# zero_board.net
KiCad netlist of a schematic drawn in EAGLE
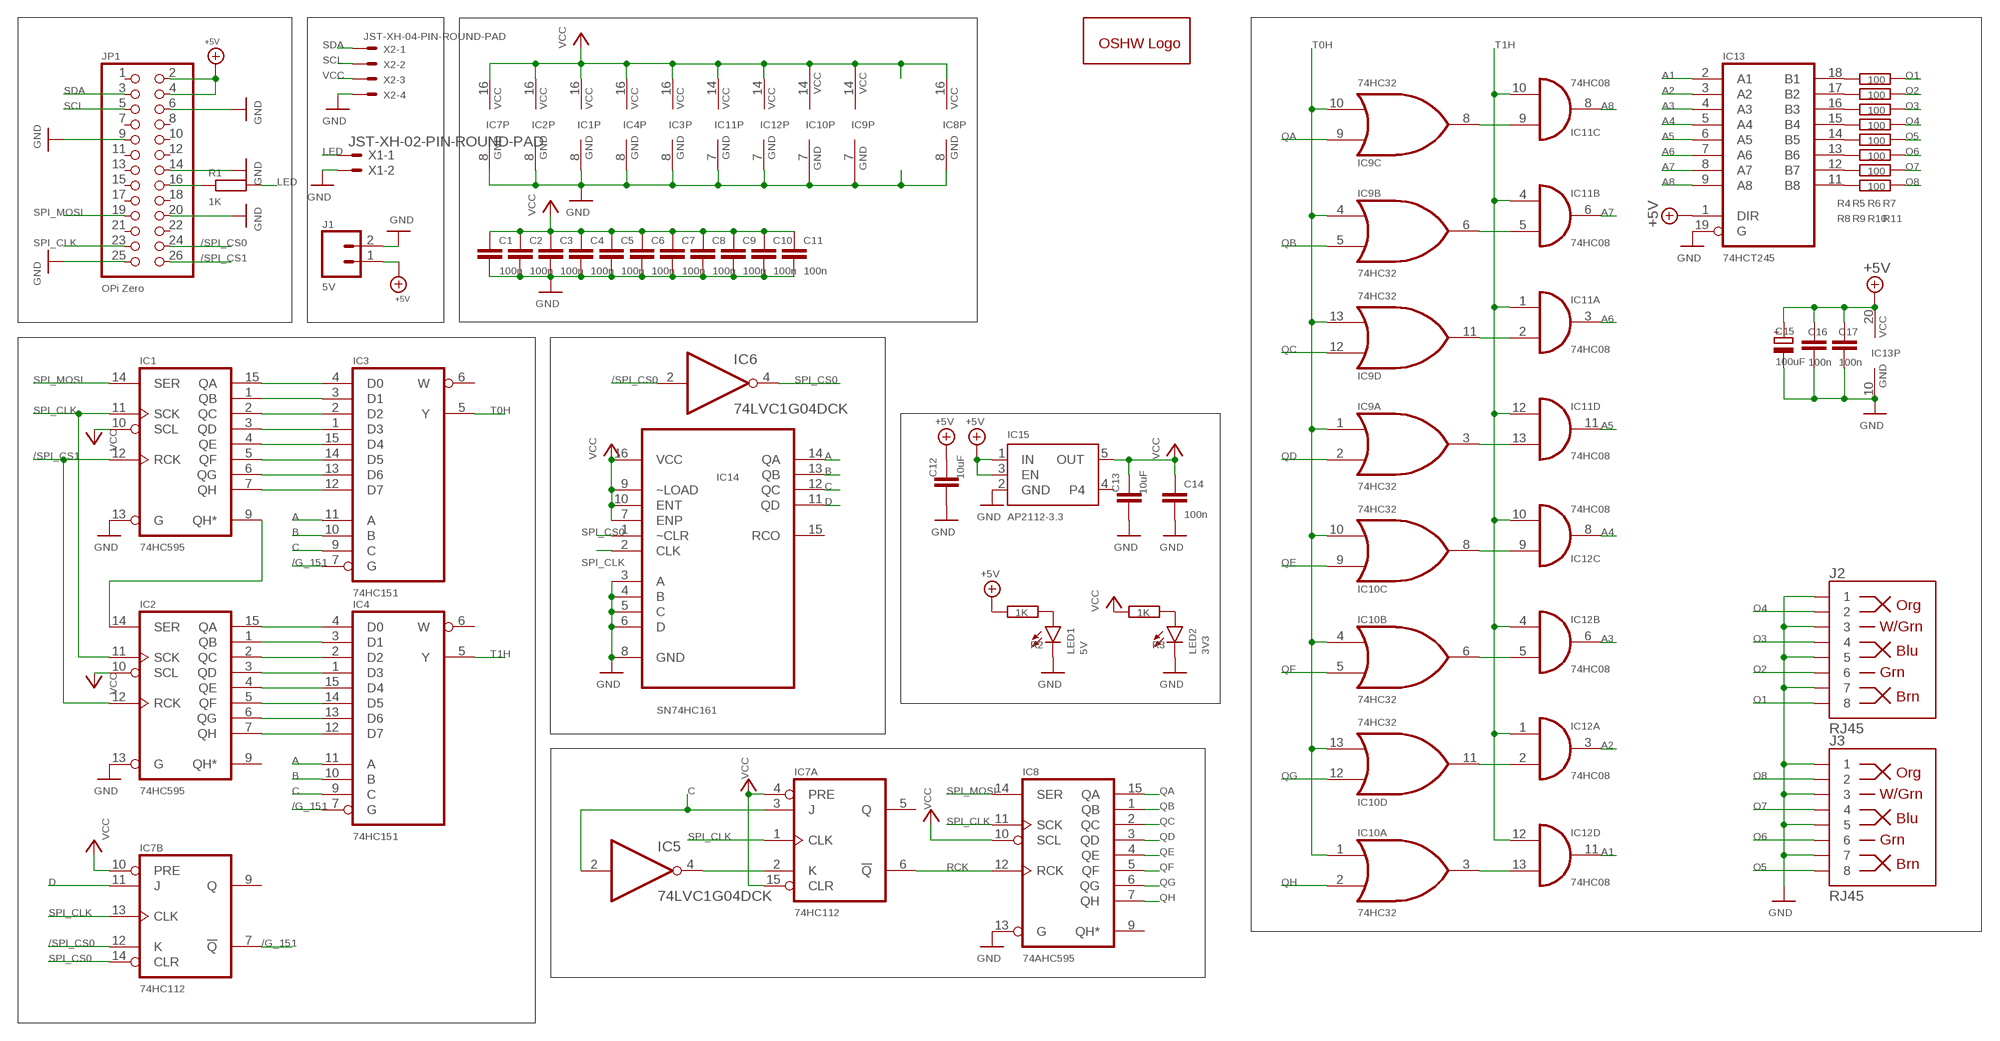
[diagram p0: schematic, sheet 1]

(export (version "E")
  (design (tool "Eeschema 10.0.6"))
  (components
    (comp (ref "C1")
      (value "100n")
      (footprint "eagle-import:C0603")
      (libsource (lib "eagle-import") (part "C-EUC0603"))
    )
    (comp (ref "C2")
      (value "100n")
      (footprint "eagle-import:C0603")
      (libsource (lib "eagle-import") (part "C-EUC0603"))
    )
    (comp (ref "C3")
      (value "100n")
      (footprint "eagle-import:C0603")
      (libsource (lib "eagle-import") (part "C-EUC0603"))
    )
    (comp (ref "C4")
      (value "100n")
      (footprint "eagle-import:C0603")
      (libsource (lib "eagle-import") (part "C-EUC0603"))
    )
    (comp (ref "C5")
      (value "100n")
      (footprint "eagle-import:C0603")
      (libsource (lib "eagle-import") (part "C-EUC0603"))
    )
    (comp (ref "C6")
      (value "100n")
      (footprint "eagle-import:C0603")
      (libsource (lib "eagle-import") (part "C-EUC0603"))
    )
    (comp (ref "C7")
      (value "100n")
      (footprint "eagle-import:C0603")
      (libsource (lib "eagle-import") (part "C-EUC0603"))
    )
    (comp (ref "C8")
      (value "100n")
      (footprint "eagle-import:C0603")
      (libsource (lib "eagle-import") (part "C-EUC0603"))
    )
    (comp (ref "C9")
      (value "100n")
      (footprint "eagle-import:C0603")
      (libsource (lib "eagle-import") (part "C-EUC0603"))
    )
    (comp (ref "C10")
      (value "100n")
      (footprint "eagle-import:C0603")
      (libsource (lib "eagle-import") (part "C-EUC0603"))
    )
    (comp (ref "C11")
      (value "100n")
      (footprint "eagle-import:C0603")
      (libsource (lib "eagle-import") (part "C-EUC0603"))
    )
    (comp (ref "C12")
      (value "10uF")
      (footprint "eagle-import:C0805")
      (libsource (lib "eagle-import") (part "C-EUC0805"))
    )
    (comp (ref "C13")
      (value "10uF")
      (footprint "eagle-import:C0805")
      (libsource (lib "eagle-import") (part "C-EUC0805"))
    )
    (comp (ref "C14")
      (value "100n")
      (footprint "eagle-import:C0603")
      (libsource (lib "eagle-import") (part "C-EUC0603"))
    )
    (comp (ref "C15")
      (value "100uF")
      (footprint "eagle-import:E2,5-5")
      (libsource (lib "eagle-import") (part "CPOL-EUE2.5-5"))
    )
    (comp (ref "C16")
      (value "100n")
      (footprint "eagle-import:C0603")
      (libsource (lib "eagle-import") (part "C-EUC0603"))
    )
    (comp (ref "C17")
      (value "100n")
      (footprint "eagle-import:C0603")
      (libsource (lib "eagle-import") (part "C-EUC0603"))
    )
    (comp (ref "GOLD_ORB_SM1")
      (value "OSHWLOGOLOGO5MM")
      (footprint "eagle-import:OSHW_5MM")
      (libsource (lib "eagle-import") (part "OSHWLOGOLOGO5MM"))
    )
    (comp (ref "IC1")
      (value "74HC595")
      (footprint "eagle-import:SO16")
      (libsource (lib "eagle-import") (part "74595DHC"))
    )
    (comp (ref "IC2")
      (value "74HC595")
      (footprint "eagle-import:SO16")
      (libsource (lib "eagle-import") (part "74595DHC"))
    )
    (comp (ref "IC3")
      (value "74HC151")
      (footprint "eagle-import:SO16")
      (libsource (lib "eagle-import") (part "74151DHC"))
    )
    (comp (ref "IC4")
      (value "74HC151")
      (footprint "eagle-import:SO16")
      (libsource (lib "eagle-import") (part "74151DHC"))
    )
    (comp (ref "IC5")
      (value "74LVC1G04DCK")
      (footprint "eagle-import:SC70-5")
      (libsource (lib "eagle-import") (part "741G04DCKLVC"))
    )
    (comp (ref "IC6")
      (value "74LVC1G04DCK")
      (footprint "eagle-import:SC70-5")
      (libsource (lib "eagle-import") (part "741G04DCKLVC"))
    )
    (comp (ref "IC7")
      (value "74HC112")
      (footprint "eagle-import:SO16")
      (libsource (lib "eagle-import") (part "74112DHC"))
    )
    (comp (ref "IC8")
      (value "74AHC595")
      (footprint "eagle-import:SO16")
      (libsource (lib "eagle-import") (part "74595DHC"))
    )
    (comp (ref "IC9")
      (value "74HC32")
      (footprint "eagle-import:SO14")
      (libsource (lib "eagle-import") (part "7432DLS"))
    )
    (comp (ref "IC10")
      (value "74HC32")
      (footprint "eagle-import:SO14")
      (libsource (lib "eagle-import") (part "7432DLS"))
    )
    (comp (ref "IC11")
      (value "74HC08")
      (footprint "eagle-import:SO14")
      (libsource (lib "eagle-import") (part "7408DHC"))
    )
    (comp (ref "IC12")
      (value "74HC08")
      (footprint "eagle-import:SO14")
      (libsource (lib "eagle-import") (part "7408DHC"))
    )
    (comp (ref "IC13")
      (value "74HCT245")
      (footprint "eagle-import:SO20W")
      (libsource (lib "eagle-import") (part "74245DWACT"))
    )
    (comp (ref "IC14")
      (value "SN74HC161")
      (footprint "eagle-import:SOIC127P600X175-16N")
      (fields (field (name "MF") "Texas Instruments") (field (name "MP") "SN74HC161DR"))
      (libsource (lib "eagle-import") (part "SN74HC161DR"))
    )
    (comp (ref "IC15")
      (value "AP2112-3.3")
      (footprint "eagle-import:SOT23-5")
      (libsource (lib "eagle-import") (part "VREG_SOT23-5"))
    )
    (comp (ref "J1")
      (value "5V")
      (footprint "eagle-import:SCREWTERMINAL-3.5MM-2")
      (libsource (lib "eagle-import") (part "CONN_023.5MM"))
    )
    (comp (ref "J2")
      (value "RJ45")
      (footprint "eagle-import:RJ45-8")
      (libsource (lib "eagle-import") (part "RJ45-8"))
    )
    (comp (ref "J3")
      (value "RJ45")
      (footprint "eagle-import:RJ45-8")
      (libsource (lib "eagle-import") (part "RJ45-8"))
    )
    (comp (ref "JP1")
      (value "OPi Zero")
      (footprint "eagle-import:2X13")
      (libsource (lib "eagle-import") (part "PINHD-2X13"))
    )
    (comp (ref "LED1")
      (value "5V")
      (footprint "eagle-import:CHIP-LED0603")
      (libsource (lib "eagle-import") (part "LEDCHIP-LED0603"))
    )
    (comp (ref "LED2")
      (value "3V3")
      (footprint "eagle-import:CHIP-LED0603")
      (libsource (lib "eagle-import") (part "LEDCHIP-LED0603"))
    )
    (comp (ref "R1")
      (value "1K")
      (footprint "eagle-import:R0603")
      (libsource (lib "eagle-import") (part "R-EU_R0603"))
    )
    (comp (ref "R2")
      (value "1K")
      (footprint "eagle-import:R0603")
      (libsource (lib "eagle-import") (part "R-EU_R0603"))
    )
    (comp (ref "R3")
      (value "1K")
      (footprint "eagle-import:R0603")
      (libsource (lib "eagle-import") (part "R-EU_R0603"))
    )
    (comp (ref "R4")
      (value "100")
      (footprint "eagle-import:R0603")
      (libsource (lib "eagle-import") (part "R-EU_R0603"))
    )
    (comp (ref "R5")
      (value "100")
      (footprint "eagle-import:R0603")
      (libsource (lib "eagle-import") (part "R-EU_R0603"))
    )
    (comp (ref "R6")
      (value "100")
      (footprint "eagle-import:R0603")
      (libsource (lib "eagle-import") (part "R-EU_R0603"))
    )
    (comp (ref "R7")
      (value "100")
      (footprint "eagle-import:R0603")
      (libsource (lib "eagle-import") (part "R-EU_R0603"))
    )
    (comp (ref "R8")
      (value "100")
      (footprint "eagle-import:R0603")
      (libsource (lib "eagle-import") (part "R-EU_R0603"))
    )
    (comp (ref "R9")
      (value "100")
      (footprint "eagle-import:R0603")
      (libsource (lib "eagle-import") (part "R-EU_R0603"))
    )
    (comp (ref "R10")
      (value "100")
      (footprint "eagle-import:R0603")
      (libsource (lib "eagle-import") (part "R-EU_R0603"))
    )
    (comp (ref "R11")
      (value "100")
      (footprint "eagle-import:R0603")
      (libsource (lib "eagle-import") (part "R-EU_R0603"))
    )
    (comp (ref "X1")
      (value "JST-XH-02-PIN-ROUND-PAD")
      (footprint "eagle-import:JST-XH-02-PACKAGE-ROUND-PAD")
      (libsource (lib "eagle-import") (part "JST-XH-02-PIN-ROUND-PAD"))
    )
    (comp (ref "X2")
      (value "JST-XH-04-PIN-ROUND-PAD")
      (footprint "eagle-import:JST-XH-04-PACKAGE-ROUND-PAD")
      (libsource (lib "eagle-import") (part "JST-XH-04-PIN-ROUND-PAD"))
    )
  )
  (nets
    (net (code "1") (name "+5V") (class "Default")
      (node (ref "C12") (pin "1") (pinfunction "1_1") (pintype "passive"))
      (node (ref "C15") (pin "+") (pinfunction "+_+") (pintype "passive"))
      (node (ref "C16") (pin "1") (pinfunction "1_1") (pintype "passive"))
      (node (ref "C17") (pin "1") (pinfunction "1_1") (pintype "passive"))
      (node (ref "IC13") (pin "1") (pinfunction "DIR_1") (pintype "input"))
      (node (ref "IC13") (pin "20") (pinfunction "VCC_20") (pintype "power_in"))
      (node (ref "IC15") (pin "1") (pinfunction "IN_1") (pintype "power_in"))
      (node (ref "IC15") (pin "3") (pinfunction "EN_3") (pintype "input"))
      (node (ref "J1") (pin "1") (pinfunction "1_1") (pintype "passive"))
      (node (ref "JP1") (pin "2") (pinfunction "2_2") (pintype "passive"))
      (node (ref "JP1") (pin "4") (pinfunction "4_4") (pintype "passive"))
      (node (ref "R2") (pin "1") (pinfunction "1_1") (pintype "passive"))
    )
    (net (code "2") (name "/A") (class "Default")
      (node (ref "IC14") (pin "14") (pinfunction "QA_14") (pintype "output"))
      (node (ref "IC3") (pin "11") (pinfunction "A_11") (pintype "input"))
      (node (ref "IC4") (pin "11") (pinfunction "A_11") (pintype "input"))
    )
    (net (code "3") (name "/A1") (class "Default")
      (node (ref "IC12") (pin "11") (pinfunction "O_11") (pintype "output"))
      (node (ref "IC13") (pin "2") (pinfunction "A1_2") (pintype "bidirectional"))
    )
    (net (code "4") (name "/A2") (class "Default")
      (node (ref "IC12") (pin "3") (pinfunction "O_3") (pintype "output"))
      (node (ref "IC13") (pin "3") (pinfunction "A2_3") (pintype "bidirectional"))
    )
    (net (code "5") (name "/A3") (class "Default")
      (node (ref "IC12") (pin "6") (pinfunction "O_6") (pintype "output"))
      (node (ref "IC13") (pin "4") (pinfunction "A3_4") (pintype "bidirectional"))
    )
    (net (code "6") (name "/A4") (class "Default")
      (node (ref "IC12") (pin "8") (pinfunction "O_8") (pintype "output"))
      (node (ref "IC13") (pin "5") (pinfunction "A4_5") (pintype "bidirectional"))
    )
    (net (code "7") (name "/A5") (class "Default")
      (node (ref "IC11") (pin "11") (pinfunction "O_11") (pintype "output"))
      (node (ref "IC13") (pin "6") (pinfunction "A5_6") (pintype "bidirectional"))
    )
    (net (code "8") (name "/A6") (class "Default")
      (node (ref "IC11") (pin "3") (pinfunction "O_3") (pintype "output"))
      (node (ref "IC13") (pin "7") (pinfunction "A6_7") (pintype "bidirectional"))
    )
    (net (code "9") (name "/A7") (class "Default")
      (node (ref "IC11") (pin "6") (pinfunction "O_6") (pintype "output"))
      (node (ref "IC13") (pin "8") (pinfunction "A7_8") (pintype "bidirectional"))
    )
    (net (code "10") (name "/A8") (class "Default")
      (node (ref "IC11") (pin "8") (pinfunction "O_8") (pintype "output"))
      (node (ref "IC13") (pin "9") (pinfunction "A8_9") (pintype "bidirectional"))
    )
    (net (code "11") (name "/B") (class "Default")
      (node (ref "IC14") (pin "13") (pinfunction "QB_13") (pintype "output"))
      (node (ref "IC3") (pin "10") (pinfunction "B_10") (pintype "input"))
      (node (ref "IC4") (pin "10") (pinfunction "B_10") (pintype "input"))
    )
    (net (code "12") (name "/C") (class "Default")
      (node (ref "IC14") (pin "12") (pinfunction "QC_12") (pintype "output"))
      (node (ref "IC3") (pin "9") (pinfunction "C_9") (pintype "input"))
      (node (ref "IC4") (pin "9") (pinfunction "C_9") (pintype "input"))
      (node (ref "IC5") (pin "2") (pinfunction "I_2") (pintype "input"))
      (node (ref "IC7") (pin "3") (pinfunction "J_3") (pintype "input"))
    )
    (net (code "13") (name "/D") (class "Default")
      (node (ref "IC14") (pin "11") (pinfunction "QD_11") (pintype "output"))
      (node (ref "IC7") (pin "11") (pinfunction "J_11") (pintype "input"))
    )
    (net (code "14") (name "/LED") (class "Default")
      (node (ref "R1") (pin "2") (pinfunction "2_2") (pintype "passive"))
      (node (ref "X1") (pin "1") (pinfunction "S_1") (pintype "passive"))
    )
    (net (code "15") (name "/O1") (class "Default")
      (node (ref "J2") (pin "8") (pinfunction "8_8") (pintype "bidirectional"))
      (node (ref "R4") (pin "2") (pinfunction "2_2") (pintype "passive"))
    )
    (net (code "16") (name "/O2") (class "Default")
      (node (ref "J2") (pin "6") (pinfunction "6_6") (pintype "bidirectional"))
      (node (ref "R5") (pin "2") (pinfunction "2_2") (pintype "passive"))
    )
    (net (code "17") (name "/O3") (class "Default")
      (node (ref "J2") (pin "4") (pinfunction "4_4") (pintype "bidirectional"))
      (node (ref "R6") (pin "2") (pinfunction "2_2") (pintype "passive"))
    )
    (net (code "18") (name "/O4") (class "Default")
      (node (ref "J2") (pin "2") (pinfunction "2_2") (pintype "bidirectional"))
      (node (ref "R7") (pin "2") (pinfunction "2_2") (pintype "passive"))
    )
    (net (code "19") (name "/O5") (class "Default")
      (node (ref "J3") (pin "8") (pinfunction "8_8") (pintype "bidirectional"))
      (node (ref "R8") (pin "2") (pinfunction "2_2") (pintype "passive"))
    )
    (net (code "20") (name "/O6") (class "Default")
      (node (ref "J3") (pin "6") (pinfunction "6_6") (pintype "bidirectional"))
      (node (ref "R9") (pin "2") (pinfunction "2_2") (pintype "passive"))
    )
    (net (code "21") (name "/O7") (class "Default")
      (node (ref "J3") (pin "4") (pinfunction "4_4") (pintype "bidirectional"))
      (node (ref "R10") (pin "2") (pinfunction "2_2") (pintype "passive"))
    )
    (net (code "22") (name "/O8") (class "Default")
      (node (ref "J3") (pin "2") (pinfunction "2_2") (pintype "bidirectional"))
      (node (ref "R11") (pin "2") (pinfunction "2_2") (pintype "passive"))
    )
    (net (code "23") (name "/QA") (class "Default")
      (node (ref "IC8") (pin "15") (pinfunction "QA_15") (pintype "tri_state"))
      (node (ref "IC9") (pin "9") (pinfunction "I0_9") (pintype "input"))
    )
    (net (code "24") (name "/QB") (class "Default")
      (node (ref "IC8") (pin "1") (pinfunction "QB_1") (pintype "tri_state"))
      (node (ref "IC9") (pin "5") (pinfunction "I1_5") (pintype "input"))
    )
    (net (code "25") (name "/QC") (class "Default")
      (node (ref "IC8") (pin "2") (pinfunction "QC_2") (pintype "tri_state"))
      (node (ref "IC9") (pin "12") (pinfunction "I0_12") (pintype "input"))
    )
    (net (code "26") (name "/QD") (class "Default")
      (node (ref "IC8") (pin "3") (pinfunction "QD_3") (pintype "tri_state"))
      (node (ref "IC9") (pin "2") (pinfunction "I1_2") (pintype "input"))
    )
    (net (code "27") (name "/QE") (class "Default")
      (node (ref "IC10") (pin "9") (pinfunction "I0_9") (pintype "input"))
      (node (ref "IC8") (pin "4") (pinfunction "QE_4") (pintype "tri_state"))
    )
    (net (code "28") (name "/QF") (class "Default")
      (node (ref "IC10") (pin "5") (pinfunction "I1_5") (pintype "input"))
      (node (ref "IC8") (pin "5") (pinfunction "QF_5") (pintype "tri_state"))
    )
    (net (code "29") (name "/QG") (class "Default")
      (node (ref "IC10") (pin "12") (pinfunction "I0_12") (pintype "input"))
      (node (ref "IC8") (pin "6") (pinfunction "QG_6") (pintype "tri_state"))
    )
    (net (code "30") (name "/QH") (class "Default")
      (node (ref "IC10") (pin "2") (pinfunction "I1_2") (pintype "input"))
      (node (ref "IC8") (pin "7") (pinfunction "QH_7") (pintype "tri_state"))
    )
    (net (code "31") (name "/RCK") (class "Default")
      (node (ref "IC7") (pin "6") (pinfunction "~{Q}_6") (pintype "output"))
      (node (ref "IC8") (pin "12") (pinfunction "RCK_12") (pintype "input"))
    )
    (net (code "32") (name "/SCL") (class "Default")
      (node (ref "JP1") (pin "5") (pinfunction "5_5") (pintype "passive"))
      (node (ref "X2") (pin "2") (pinfunction "S_2") (pintype "passive"))
    )
    (net (code "33") (name "/SDA") (class "Default")
      (node (ref "JP1") (pin "3") (pinfunction "3_3") (pintype "passive"))
      (node (ref "X2") (pin "1") (pinfunction "S_1") (pintype "passive"))
    )
    (net (code "34") (name "/SPI_CLK") (class "Default")
      (node (ref "IC1") (pin "11") (pinfunction "SCK_11") (pintype "input"))
      (node (ref "IC14") (pin "2") (pinfunction "CLK_2") (pintype "input"))
      (node (ref "IC2") (pin "11") (pinfunction "SCK_11") (pintype "input"))
      (node (ref "IC7") (pin "1") (pinfunction "CLK_1") (pintype "input"))
      (node (ref "IC7") (pin "13") (pinfunction "CLK_13") (pintype "input"))
      (node (ref "IC8") (pin "11") (pinfunction "SCK_11") (pintype "input"))
      (node (ref "JP1") (pin "23") (pinfunction "23_23") (pintype "passive"))
    )
    (net (code "35") (name "/SPI_CS0") (class "Default")
      (node (ref "IC14") (pin "1") (pinfunction "~{CLR}_1") (pintype "input"))
      (node (ref "IC6") (pin "4") (pinfunction "O_4") (pintype "output"))
      (node (ref "IC7") (pin "14") (pinfunction "CLR_14") (pintype "input"))
    )
    (net (code "36") (name "/SPI_MOSI") (class "Default")
      (node (ref "IC1") (pin "14") (pinfunction "SER_14") (pintype "input"))
      (node (ref "IC8") (pin "14") (pinfunction "SER_14") (pintype "input"))
      (node (ref "JP1") (pin "19") (pinfunction "19_19") (pintype "passive"))
    )
    (net (code "37") (name "/T0H") (class "Default")
      (node (ref "IC10") (pin "1") (pinfunction "I0_1") (pintype "input"))
      (node (ref "IC10") (pin "10") (pinfunction "I1_10") (pintype "input"))
      (node (ref "IC10") (pin "13") (pinfunction "I1_13") (pintype "input"))
      (node (ref "IC10") (pin "4") (pinfunction "I0_4") (pintype "input"))
      (node (ref "IC3") (pin "5") (pinfunction "Y_5") (pintype "output"))
      (node (ref "IC9") (pin "1") (pinfunction "I0_1") (pintype "input"))
      (node (ref "IC9") (pin "10") (pinfunction "I1_10") (pintype "input"))
      (node (ref "IC9") (pin "13") (pinfunction "I1_13") (pintype "input"))
      (node (ref "IC9") (pin "4") (pinfunction "I0_4") (pintype "input"))
    )
    (net (code "38") (name "/T1H") (class "Default")
      (node (ref "IC11") (pin "1") (pinfunction "I0_1") (pintype "input"))
      (node (ref "IC11") (pin "10") (pinfunction "I1_10") (pintype "input"))
      (node (ref "IC11") (pin "12") (pinfunction "I0_12") (pintype "input"))
      (node (ref "IC11") (pin "4") (pinfunction "I0_4") (pintype "input"))
      (node (ref "IC12") (pin "1") (pinfunction "I0_1") (pintype "input"))
      (node (ref "IC12") (pin "10") (pinfunction "I1_10") (pintype "input"))
      (node (ref "IC12") (pin "12") (pinfunction "I0_12") (pintype "input"))
      (node (ref "IC12") (pin "4") (pinfunction "I0_4") (pintype "input"))
      (node (ref "IC4") (pin "5") (pinfunction "Y_5") (pintype "output"))
    )
    (net (code "39") (name "/{slash}G_151") (class "Default")
      (node (ref "IC3") (pin "7") (pinfunction "G_7") (pintype "input"))
      (node (ref "IC4") (pin "7") (pinfunction "G_7") (pintype "input"))
      (node (ref "IC7") (pin "7") (pinfunction "~{Q}_7") (pintype "output"))
    )
    (net (code "40") (name "/{slash}SPI_CS0") (class "Default")
      (node (ref "IC6") (pin "2") (pinfunction "I_2") (pintype "input"))
      (node (ref "IC7") (pin "12") (pinfunction "K_12") (pintype "input"))
      (node (ref "JP1") (pin "24") (pinfunction "24_24") (pintype "passive"))
    )
    (net (code "41") (name "/{slash}SPI_CS1") (class "Default")
      (node (ref "IC1") (pin "12") (pinfunction "RCK_12") (pintype "input"))
      (node (ref "IC2") (pin "12") (pinfunction "RCK_12") (pintype "input"))
      (node (ref "JP1") (pin "26") (pinfunction "26_26") (pintype "passive"))
    )
    (net (code "42") (name "GND") (class "Default")
      (node (ref "C1") (pin "2") (pinfunction "2_2") (pintype "passive"))
      (node (ref "C10") (pin "2") (pinfunction "2_2") (pintype "passive"))
      (node (ref "C11") (pin "2") (pinfunction "2_2") (pintype "passive"))
      (node (ref "C12") (pin "2") (pinfunction "2_2") (pintype "passive"))
      (node (ref "C13") (pin "2") (pinfunction "2_2") (pintype "passive"))
      (node (ref "C14") (pin "2") (pinfunction "2_2") (pintype "passive"))
      (node (ref "C15") (pin "-") (pinfunction "-_-") (pintype "passive"))
      (node (ref "C16") (pin "2") (pinfunction "2_2") (pintype "passive"))
      (node (ref "C17") (pin "2") (pinfunction "2_2") (pintype "passive"))
      (node (ref "C2") (pin "2") (pinfunction "2_2") (pintype "passive"))
      (node (ref "C3") (pin "2") (pinfunction "2_2") (pintype "passive"))
      (node (ref "C4") (pin "2") (pinfunction "2_2") (pintype "passive"))
      (node (ref "C5") (pin "2") (pinfunction "2_2") (pintype "passive"))
      (node (ref "C6") (pin "2") (pinfunction "2_2") (pintype "passive"))
      (node (ref "C7") (pin "2") (pinfunction "2_2") (pintype "passive"))
      (node (ref "C8") (pin "2") (pinfunction "2_2") (pintype "passive"))
      (node (ref "C9") (pin "2") (pinfunction "2_2") (pintype "passive"))
      (node (ref "IC1") (pin "13") (pinfunction "G_13") (pintype "input"))
      (node (ref "IC1") (pin "8") (pinfunction "GND_8") (pintype "power_in"))
      (node (ref "IC10") (pin "7") (pinfunction "GND_7") (pintype "power_in"))
      (node (ref "IC11") (pin "7") (pinfunction "GND_7") (pintype "power_in"))
      (node (ref "IC12") (pin "7") (pinfunction "GND_7") (pintype "power_in"))
      (node (ref "IC13") (pin "10") (pinfunction "GND_10") (pintype "power_in"))
      (node (ref "IC13") (pin "19") (pinfunction "G_19") (pintype "input"))
      (node (ref "IC14") (pin "3") (pinfunction "A_3") (pintype "input"))
      (node (ref "IC14") (pin "4") (pinfunction "B_4") (pintype "input"))
      (node (ref "IC14") (pin "5") (pinfunction "C_5") (pintype "input"))
      (node (ref "IC14") (pin "6") (pinfunction "D_6") (pintype "input"))
      (node (ref "IC14") (pin "8") (pinfunction "GND_8") (pintype "passive"))
      (node (ref "IC15") (pin "2") (pinfunction "GND_2") (pintype "power_in"))
      (node (ref "IC2") (pin "13") (pinfunction "G_13") (pintype "input"))
      (node (ref "IC2") (pin "8") (pinfunction "GND_8") (pintype "power_in"))
      (node (ref "IC3") (pin "8") (pinfunction "GND_8") (pintype "power_in"))
      (node (ref "IC4") (pin "8") (pinfunction "GND_8") (pintype "power_in"))
      (node (ref "IC7") (pin "8") (pinfunction "GND_8") (pintype "power_in"))
      (node (ref "IC8") (pin "13") (pinfunction "G_13") (pintype "input"))
      (node (ref "IC8") (pin "8") (pinfunction "GND_8") (pintype "power_in"))
      (node (ref "IC9") (pin "7") (pinfunction "GND_7") (pintype "power_in"))
      (node (ref "J1") (pin "2") (pinfunction "2_2") (pintype "passive"))
      (node (ref "J2") (pin "1") (pinfunction "1_1") (pintype "bidirectional"))
      (node (ref "J2") (pin "3") (pinfunction "3_3") (pintype "bidirectional"))
      (node (ref "J2") (pin "5") (pinfunction "5_5") (pintype "bidirectional"))
      (node (ref "J2") (pin "7") (pinfunction "7_7") (pintype "bidirectional"))
      (node (ref "J3") (pin "1") (pinfunction "1_1") (pintype "bidirectional"))
      (node (ref "J3") (pin "3") (pinfunction "3_3") (pintype "bidirectional"))
      (node (ref "J3") (pin "5") (pinfunction "5_5") (pintype "bidirectional"))
      (node (ref "J3") (pin "7") (pinfunction "7_7") (pintype "bidirectional"))
      (node (ref "JP1") (pin "14") (pinfunction "14_14") (pintype "passive"))
      (node (ref "JP1") (pin "20") (pinfunction "20_20") (pintype "passive"))
      (node (ref "JP1") (pin "25") (pinfunction "25_25") (pintype "passive"))
      (node (ref "JP1") (pin "6") (pinfunction "6_6") (pintype "passive"))
      (node (ref "JP1") (pin "9") (pinfunction "9_9") (pintype "passive"))
      (node (ref "LED1") (pin "C") (pinfunction "C_C") (pintype "passive"))
      (node (ref "LED2") (pin "C") (pinfunction "C_C") (pintype "passive"))
      (node (ref "X1") (pin "2") (pinfunction "S_2") (pintype "passive"))
      (node (ref "X2") (pin "4") (pinfunction "S_4") (pintype "passive"))
    )
    (net (code "43") (name "Net-(IC1A-QA)") (class "Default")
      (node (ref "IC1") (pin "15") (pinfunction "QA_15") (pintype "tri_state"))
      (node (ref "IC3") (pin "4") (pinfunction "D0_4") (pintype "input"))
    )
    (net (code "44") (name "Net-(IC1A-QB)") (class "Default")
      (node (ref "IC1") (pin "1") (pinfunction "QB_1") (pintype "tri_state"))
      (node (ref "IC3") (pin "3") (pinfunction "D1_3") (pintype "input"))
    )
    (net (code "45") (name "Net-(IC1A-QC)") (class "Default")
      (node (ref "IC1") (pin "2") (pinfunction "QC_2") (pintype "tri_state"))
      (node (ref "IC3") (pin "2") (pinfunction "D2_2") (pintype "input"))
    )
    (net (code "46") (name "Net-(IC1A-QD)") (class "Default")
      (node (ref "IC1") (pin "3") (pinfunction "QD_3") (pintype "tri_state"))
      (node (ref "IC3") (pin "1") (pinfunction "D3_1") (pintype "input"))
    )
    (net (code "47") (name "Net-(IC1A-QE)") (class "Default")
      (node (ref "IC1") (pin "4") (pinfunction "QE_4") (pintype "tri_state"))
      (node (ref "IC3") (pin "15") (pinfunction "D4_15") (pintype "input"))
    )
    (net (code "48") (name "Net-(IC1A-QF)") (class "Default")
      (node (ref "IC1") (pin "5") (pinfunction "QF_5") (pintype "tri_state"))
      (node (ref "IC3") (pin "14") (pinfunction "D5_14") (pintype "input"))
    )
    (net (code "49") (name "Net-(IC1A-QG)") (class "Default")
      (node (ref "IC1") (pin "6") (pinfunction "QG_6") (pintype "tri_state"))
      (node (ref "IC3") (pin "13") (pinfunction "D6_13") (pintype "input"))
    )
    (net (code "50") (name "Net-(IC1A-QH)") (class "Default")
      (node (ref "IC1") (pin "7") (pinfunction "QH_7") (pintype "tri_state"))
      (node (ref "IC3") (pin "12") (pinfunction "D7_12") (pintype "input"))
    )
    (net (code "51") (name "Net-(IC1A-QH*)") (class "Default")
      (node (ref "IC1") (pin "9") (pinfunction "QH*_9") (pintype "tri_state"))
      (node (ref "IC2") (pin "14") (pinfunction "SER_14") (pintype "input"))
    )
    (net (code "52") (name "Net-(IC2A-QA)") (class "Default")
      (node (ref "IC2") (pin "15") (pinfunction "QA_15") (pintype "tri_state"))
      (node (ref "IC4") (pin "4") (pinfunction "D0_4") (pintype "input"))
    )
    (net (code "53") (name "Net-(IC2A-QB)") (class "Default")
      (node (ref "IC2") (pin "1") (pinfunction "QB_1") (pintype "tri_state"))
      (node (ref "IC4") (pin "3") (pinfunction "D1_3") (pintype "input"))
    )
    (net (code "54") (name "Net-(IC2A-QC)") (class "Default")
      (node (ref "IC2") (pin "2") (pinfunction "QC_2") (pintype "tri_state"))
      (node (ref "IC4") (pin "2") (pinfunction "D2_2") (pintype "input"))
    )
    (net (code "55") (name "Net-(IC2A-QD)") (class "Default")
      (node (ref "IC2") (pin "3") (pinfunction "QD_3") (pintype "tri_state"))
      (node (ref "IC4") (pin "1") (pinfunction "D3_1") (pintype "input"))
    )
    (net (code "56") (name "Net-(IC2A-QE)") (class "Default")
      (node (ref "IC2") (pin "4") (pinfunction "QE_4") (pintype "tri_state"))
      (node (ref "IC4") (pin "15") (pinfunction "D4_15") (pintype "input"))
    )
    (net (code "57") (name "Net-(IC2A-QF)") (class "Default")
      (node (ref "IC2") (pin "5") (pinfunction "QF_5") (pintype "tri_state"))
      (node (ref "IC4") (pin "14") (pinfunction "D5_14") (pintype "input"))
    )
    (net (code "58") (name "Net-(IC2A-QG)") (class "Default")
      (node (ref "IC2") (pin "6") (pinfunction "QG_6") (pintype "tri_state"))
      (node (ref "IC4") (pin "13") (pinfunction "D6_13") (pintype "input"))
    )
    (net (code "59") (name "Net-(IC2A-QH)") (class "Default")
      (node (ref "IC2") (pin "7") (pinfunction "QH_7") (pintype "tri_state"))
      (node (ref "IC4") (pin "12") (pinfunction "D7_12") (pintype "input"))
    )
    (net (code "60") (name "Net-(IC5A-O)") (class "Default")
      (node (ref "IC5") (pin "4") (pinfunction "O_4") (pintype "output"))
      (node (ref "IC7") (pin "2") (pinfunction "K_2") (pintype "input"))
    )
    (net (code "61") (name "Net-(IC10A-O)") (class "Default")
      (node (ref "IC10") (pin "3") (pinfunction "O_3") (pintype "output"))
      (node (ref "IC12") (pin "13") (pinfunction "I1_13") (pintype "input"))
    )
    (net (code "62") (name "Net-(IC10B-O)") (class "Default")
      (node (ref "IC10") (pin "6") (pinfunction "O_6") (pintype "output"))
      (node (ref "IC12") (pin "5") (pinfunction "I1_5") (pintype "input"))
    )
    (net (code "63") (name "Net-(IC10C-O)") (class "Default")
      (node (ref "IC10") (pin "8") (pinfunction "O_8") (pintype "output"))
      (node (ref "IC12") (pin "9") (pinfunction "I0_9") (pintype "input"))
    )
    (net (code "64") (name "Net-(IC10D-O)") (class "Default")
      (node (ref "IC10") (pin "11") (pinfunction "O_11") (pintype "output"))
      (node (ref "IC12") (pin "2") (pinfunction "I1_2") (pintype "input"))
    )
    (net (code "65") (name "Net-(IC11A-I1)") (class "Default")
      (node (ref "IC11") (pin "2") (pinfunction "I1_2") (pintype "input"))
      (node (ref "IC9") (pin "11") (pinfunction "O_11") (pintype "output"))
    )
    (net (code "66") (name "Net-(IC11B-I1)") (class "Default")
      (node (ref "IC11") (pin "5") (pinfunction "I1_5") (pintype "input"))
      (node (ref "IC9") (pin "6") (pinfunction "O_6") (pintype "output"))
    )
    (net (code "67") (name "Net-(IC11C-I0)") (class "Default")
      (node (ref "IC11") (pin "9") (pinfunction "I0_9") (pintype "input"))
      (node (ref "IC9") (pin "8") (pinfunction "O_8") (pintype "output"))
    )
    (net (code "68") (name "Net-(IC11D-I1)") (class "Default")
      (node (ref "IC11") (pin "13") (pinfunction "I1_13") (pintype "input"))
      (node (ref "IC9") (pin "3") (pinfunction "O_3") (pintype "output"))
    )
    (net (code "69") (name "Net-(IC13A-B1)") (class "Default")
      (node (ref "IC13") (pin "18") (pinfunction "B1_18") (pintype "bidirectional"))
      (node (ref "R4") (pin "1") (pinfunction "1_1") (pintype "passive"))
    )
    (net (code "70") (name "Net-(IC13A-B2)") (class "Default")
      (node (ref "IC13") (pin "17") (pinfunction "B2_17") (pintype "bidirectional"))
      (node (ref "R5") (pin "1") (pinfunction "1_1") (pintype "passive"))
    )
    (net (code "71") (name "Net-(IC13A-B3)") (class "Default")
      (node (ref "IC13") (pin "16") (pinfunction "B3_16") (pintype "bidirectional"))
      (node (ref "R6") (pin "1") (pinfunction "1_1") (pintype "passive"))
    )
    (net (code "72") (name "Net-(IC13A-B4)") (class "Default")
      (node (ref "IC13") (pin "15") (pinfunction "B4_15") (pintype "bidirectional"))
      (node (ref "R7") (pin "1") (pinfunction "1_1") (pintype "passive"))
    )
    (net (code "73") (name "Net-(IC13A-B5)") (class "Default")
      (node (ref "IC13") (pin "14") (pinfunction "B5_14") (pintype "bidirectional"))
      (node (ref "R8") (pin "1") (pinfunction "1_1") (pintype "passive"))
    )
    (net (code "74") (name "Net-(IC13A-B6)") (class "Default")
      (node (ref "IC13") (pin "13") (pinfunction "B6_13") (pintype "bidirectional"))
      (node (ref "R9") (pin "1") (pinfunction "1_1") (pintype "passive"))
    )
    (net (code "75") (name "Net-(IC13A-B7)") (class "Default")
      (node (ref "IC13") (pin "12") (pinfunction "B7_12") (pintype "bidirectional"))
      (node (ref "R10") (pin "1") (pinfunction "1_1") (pintype "passive"))
    )
    (net (code "76") (name "Net-(IC13A-B8)") (class "Default")
      (node (ref "IC13") (pin "11") (pinfunction "B8_11") (pintype "bidirectional"))
      (node (ref "R11") (pin "1") (pinfunction "1_1") (pintype "passive"))
    )
    (net (code "77") (name "Net-(JP1-Pad16)") (class "Default")
      (node (ref "JP1") (pin "16") (pinfunction "16_16") (pintype "passive"))
      (node (ref "R1") (pin "1") (pinfunction "1_1") (pintype "passive"))
    )
    (net (code "78") (name "Net-(LED1-PadA)") (class "Default")
      (node (ref "LED1") (pin "A") (pinfunction "A_A") (pintype "passive"))
      (node (ref "R2") (pin "2") (pinfunction "2_2") (pintype "passive"))
    )
    (net (code "79") (name "Net-(LED2-PadA)") (class "Default")
      (node (ref "LED2") (pin "A") (pinfunction "A_A") (pintype "passive"))
      (node (ref "R3") (pin "2") (pinfunction "2_2") (pintype "passive"))
    )
    (net (code "80") (name "VCC") (class "Default")
      (node (ref "C1") (pin "1") (pinfunction "1_1") (pintype "passive"))
      (node (ref "C10") (pin "1") (pinfunction "1_1") (pintype "passive"))
      (node (ref "C11") (pin "1") (pinfunction "1_1") (pintype "passive"))
      (node (ref "C13") (pin "1") (pinfunction "1_1") (pintype "passive"))
      (node (ref "C14") (pin "1") (pinfunction "1_1") (pintype "passive"))
      (node (ref "C2") (pin "1") (pinfunction "1_1") (pintype "passive"))
      (node (ref "C3") (pin "1") (pinfunction "1_1") (pintype "passive"))
      (node (ref "C4") (pin "1") (pinfunction "1_1") (pintype "passive"))
      (node (ref "C5") (pin "1") (pinfunction "1_1") (pintype "passive"))
      (node (ref "C6") (pin "1") (pinfunction "1_1") (pintype "passive"))
      (node (ref "C7") (pin "1") (pinfunction "1_1") (pintype "passive"))
      (node (ref "C8") (pin "1") (pinfunction "1_1") (pintype "passive"))
      (node (ref "C9") (pin "1") (pinfunction "1_1") (pintype "passive"))
      (node (ref "IC1") (pin "10") (pinfunction "SCL_10") (pintype "input"))
      (node (ref "IC1") (pin "16") (pinfunction "VCC_16") (pintype "power_in"))
      (node (ref "IC10") (pin "14") (pinfunction "VCC_14") (pintype "power_in"))
      (node (ref "IC11") (pin "14") (pinfunction "VCC_14") (pintype "power_in"))
      (node (ref "IC12") (pin "14") (pinfunction "VCC_14") (pintype "power_in"))
      (node (ref "IC14") (pin "10") (pinfunction "ENT_10") (pintype "input"))
      (node (ref "IC14") (pin "16") (pinfunction "VCC_16") (pintype "power_in"))
      (node (ref "IC14") (pin "7") (pinfunction "ENP_7") (pintype "input"))
      (node (ref "IC14") (pin "9") (pinfunction "~{LOAD}_9") (pintype "input"))
      (node (ref "IC15") (pin "5") (pinfunction "OUT_5") (pintype "power_in"))
      (node (ref "IC2") (pin "10") (pinfunction "SCL_10") (pintype "input"))
      (node (ref "IC2") (pin "16") (pinfunction "VCC_16") (pintype "power_in"))
      (node (ref "IC3") (pin "16") (pinfunction "VCC_16") (pintype "power_in"))
      (node (ref "IC4") (pin "16") (pinfunction "VCC_16") (pintype "power_in"))
      (node (ref "IC7") (pin "10") (pinfunction "PRE_10") (pintype "input"))
      (node (ref "IC7") (pin "15") (pinfunction "CLR_15") (pintype "input"))
      (node (ref "IC7") (pin "16") (pinfunction "VCC_16") (pintype "power_in"))
      (node (ref "IC7") (pin "4") (pinfunction "PRE_4") (pintype "input"))
      (node (ref "IC8") (pin "10") (pinfunction "SCL_10") (pintype "input"))
      (node (ref "IC8") (pin "16") (pinfunction "VCC_16") (pintype "power_in"))
      (node (ref "IC9") (pin "14") (pinfunction "VCC_14") (pintype "power_in"))
      (node (ref "R3") (pin "1") (pinfunction "1_1") (pintype "passive"))
      (node (ref "X2") (pin "3") (pinfunction "S_3") (pintype "passive"))
    )
    (net (code "81") (name "unconnected-(IC2A-QH*-Pad9)") (class "Default")
      (node (ref "IC2") (pin "9") (pinfunction "QH*_9") (pintype "tri_state"))
    )
    (net (code "82") (name "unconnected-(IC3A-W-Pad6)") (class "Default")
      (node (ref "IC3") (pin "6") (pinfunction "W_6") (pintype "output"))
    )
    (net (code "83") (name "unconnected-(IC4A-W-Pad6)") (class "Default")
      (node (ref "IC4") (pin "6") (pinfunction "W_6") (pintype "output"))
    )
    (net (code "84") (name "unconnected-(IC7A-Q-Pad5)") (class "Default")
      (node (ref "IC7") (pin "5") (pinfunction "Q_5") (pintype "output"))
    )
    (net (code "85") (name "unconnected-(IC7B-Q-Pad9)") (class "Default")
      (node (ref "IC7") (pin "9") (pinfunction "Q_9") (pintype "output"))
    )
    (net (code "86") (name "unconnected-(IC8A-QH*-Pad9)") (class "Default")
      (node (ref "IC8") (pin "9") (pinfunction "QH*_9") (pintype "tri_state"))
    )
    (net (code "87") (name "unconnected-(IC14-RCO-Pad15)") (class "Default")
      (node (ref "IC14") (pin "15") (pinfunction "RCO_15") (pintype "output"))
    )
    (net (code "88") (name "unconnected-(IC15-P4-Pad4)") (class "Default")
      (node (ref "IC15") (pin "4") (pinfunction "P4_4") (pintype "bidirectional"))
    )
    (net (code "89") (name "unconnected-(JP1-Pad1)") (class "Default")
      (node (ref "JP1") (pin "1") (pinfunction "1_1") (pintype "passive"))
    )
    (net (code "90") (name "unconnected-(JP1-Pad7)") (class "Default")
      (node (ref "JP1") (pin "7") (pinfunction "7_7") (pintype "passive"))
    )
    (net (code "91") (name "unconnected-(JP1-Pad8)") (class "Default")
      (node (ref "JP1") (pin "8") (pinfunction "8_8") (pintype "passive"))
    )
    (net (code "92") (name "unconnected-(JP1-Pad10)") (class "Default")
      (node (ref "JP1") (pin "10") (pinfunction "10_10") (pintype "passive"))
    )
    (net (code "93") (name "unconnected-(JP1-Pad11)") (class "Default")
      (node (ref "JP1") (pin "11") (pinfunction "11_11") (pintype "passive"))
    )
    (net (code "94") (name "unconnected-(JP1-Pad12)") (class "Default")
      (node (ref "JP1") (pin "12") (pinfunction "12_12") (pintype "passive"))
    )
    (net (code "95") (name "unconnected-(JP1-Pad13)") (class "Default")
      (node (ref "JP1") (pin "13") (pinfunction "13_13") (pintype "passive"))
    )
    (net (code "96") (name "unconnected-(JP1-Pad15)") (class "Default")
      (node (ref "JP1") (pin "15") (pinfunction "15_15") (pintype "passive"))
    )
    (net (code "97") (name "unconnected-(JP1-Pad17)") (class "Default")
      (node (ref "JP1") (pin "17") (pinfunction "17_17") (pintype "passive"))
    )
    (net (code "98") (name "unconnected-(JP1-Pad18)") (class "Default")
      (node (ref "JP1") (pin "18") (pinfunction "18_18") (pintype "passive"))
    )
    (net (code "99") (name "unconnected-(JP1-Pad21)") (class "Default")
      (node (ref "JP1") (pin "21") (pinfunction "21_21") (pintype "passive"))
    )
    (net (code "100") (name "unconnected-(JP1-Pad22)") (class "Default")
      (node (ref "JP1") (pin "22") (pinfunction "22_22") (pintype "passive"))
    )
  )
)
